# Power_Monitor.net
KiCad netlist of a schematic drawn in Altium Designer
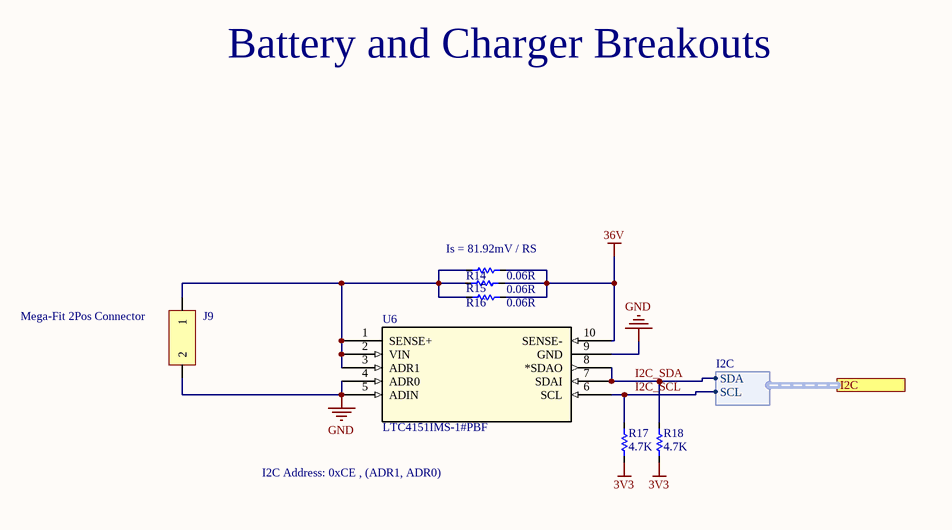
[diagram p0: Power_Monitor.SchDoc]

(export (version "E")
  (design (tool "Eeschema 10.0.6"))
  (components
    (comp (ref "J9")
      (value "Mega-Fit 2Pos Connector")
      (footprint "MegaFit-2Pos")
      (description "Molex MegaFit 2-Pos Connector")
      (libsource (lib "LaunchyRIOComponents") (part "Mega-Fit 2Pos"))
    )
    (comp (ref "R14")
      (value "0.06R")
      (footprint "0603")
      (fields (field (name "Comment") "Res"))
      (libsource (lib "Generic_Library") (part "Res"))
    )
    (comp (ref "R15")
      (value "0.06R")
      (footprint "0603")
      (fields (field (name "Comment") "Res"))
      (libsource (lib "Generic_Library") (part "Res"))
    )
    (comp (ref "R16")
      (value "0.06R")
      (footprint "0603")
      (fields (field (name "Comment") "Res"))
      (libsource (lib "Generic_Library") (part "Res"))
    )
    (comp (ref "R17")
      (value "4.7K")
      (footprint "0603")
      (fields (field (name "Comment") "Res"))
      (libsource (lib "Generic_Library") (part "Res"))
    )
    (comp (ref "R18")
      (value "4.7K")
      (footprint "0603")
      (fields (field (name "Comment") "Res"))
      (libsource (lib "Generic_Library") (part "Res"))
    )
    (comp (ref "U6")
      (value "LTC4151IMS-1#PBF")
      (footprint "MSOP-10_MS")
      (description "Imported")
      (fields
        (field (name "MANUFACTURER_PART_NUMBER") "ltc4151ims-1#pbf")
        (field (name "COPYRIGHT") "Copyright (C) 2016 Accelerated Designs. All rights reserved")
      )
      (libsource (lib "LaunchyRIOComponents") (part "LTC4151IMS-1#PBF"))
    )
  )
  (nets
    (net (code "2") (name "/I2C_SCL") (class "Default")
      (node (ref "R17") (pin "2") (pinfunction "2_2") (pintype "passive"))
      (node (ref "U6") (pin "6") (pinfunction "SCL_6") (pintype "input"))
    )
    (net (code "3") (name "/I2C_SDA") (class "Default")
      (node (ref "R18") (pin "2") (pinfunction "2_2") (pintype "passive"))
      (node (ref "U6") (pin "7") (pinfunction "SDAI_7") (pintype "input"))
      (node (ref "U6") (pin "8") (pinfunction "*SDAO_8") (pintype "output"))
    )
    (net (code "5") (name "3V3") (class "Default")
      (node (ref "R17") (pin "1") (pinfunction "1_1") (pintype "passive"))
      (node (ref "R18") (pin "1") (pinfunction "1_1") (pintype "passive"))
    )
    (net (code "6") (name "36V") (class "Default")
      (node (ref "R14") (pin "2") (pinfunction "2_2") (pintype "passive"))
      (node (ref "R15") (pin "2") (pinfunction "2_2") (pintype "passive"))
      (node (ref "R16") (pin "2") (pinfunction "2_2") (pintype "passive"))
      (node (ref "U6") (pin "10") (pinfunction "SENSE-_10") (pintype "input"))
    )
    (net (code "7") (name "GND") (class "Default")
      (node (ref "J9") (pin "2") (pinfunction "2_2") (pintype "passive"))
      (node (ref "U6") (pin "4") (pinfunction "ADR0_4") (pintype "input"))
      (node (ref "U6") (pin "5") (pinfunction "ADIN_5") (pintype "input"))
      (node (ref "U6") (pin "9") (pinfunction "GND_9") (pintype "power_in"))
    )
    (net (code "8") (name "Net-(U6-ADR1)") (class "Default")
      (node (ref "J9") (pin "1") (pinfunction "1_1") (pintype "passive"))
      (node (ref "R14") (pin "1") (pinfunction "1_1") (pintype "passive"))
      (node (ref "R15") (pin "1") (pinfunction "1_1") (pintype "passive"))
      (node (ref "R16") (pin "1") (pinfunction "1_1") (pintype "passive"))
      (node (ref "U6") (pin "1") (pinfunction "SENSE+_1") (pintype "passive"))
      (node (ref "U6") (pin "2") (pinfunction "VIN_2") (pintype "input"))
      (node (ref "U6") (pin "3") (pinfunction "ADR1_3") (pintype "input"))
    )
  )
)
